# ESP12Block.net
KiCad netlist of a schematic drawn in EAGLE
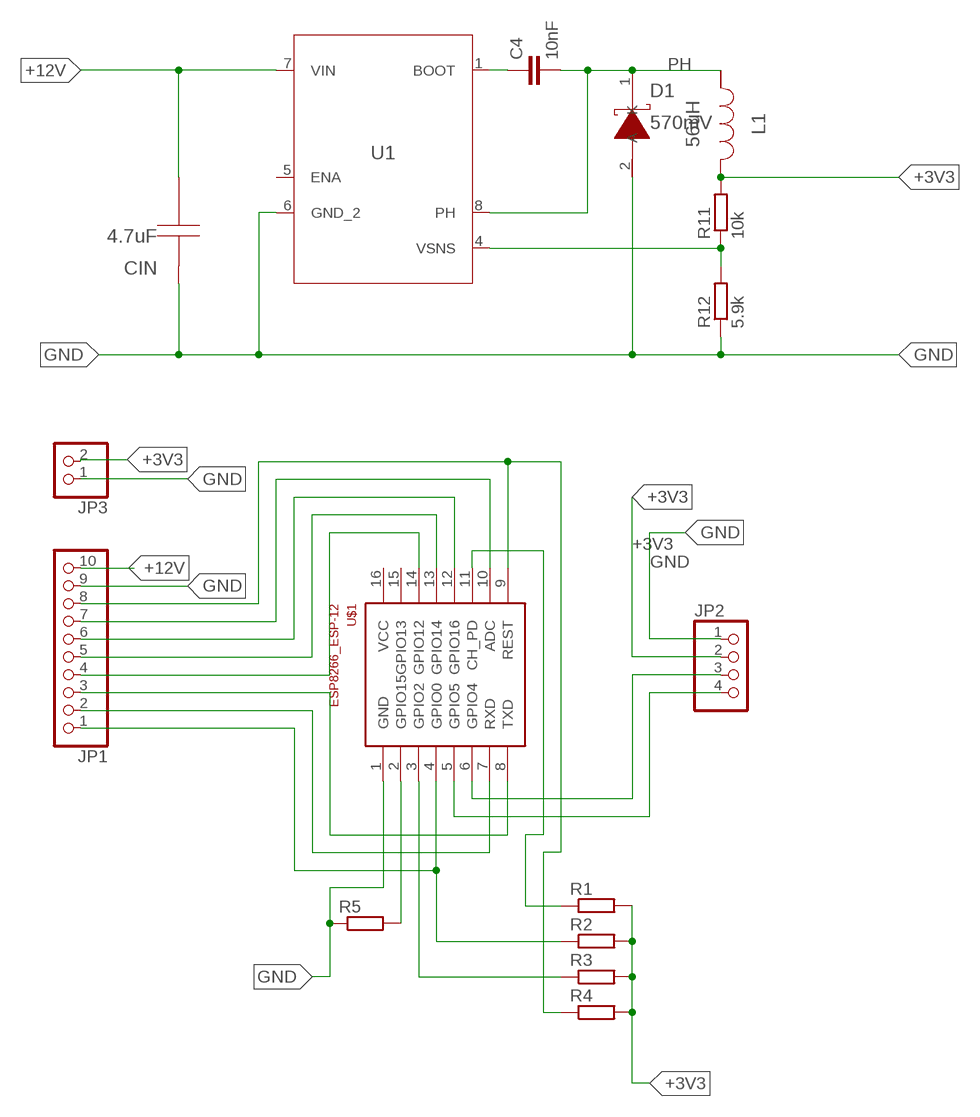
[diagram p0: schematic, sheet 1]

(export (version "E")
  (design (tool "Eeschema 10.0.6"))
  (components
    (comp (ref "C4")
      (value "10nF")
      (footprint "eagle-import:C0805")
      (libsource (lib "eagle-import") (part "C-EUC0805"))
    )
    (comp (ref "CIN")
      (value "4.7uF")
      (footprint "eagle-import:1206")
      (fields (field (name "MANUFACTURER_PART_NUMBER") "GRM31CR71H475KA12L"))
      (libsource (lib "eagle-import") (part "GRM31CR71H475KA12L"))
    )
    (comp (ref "D1")
      (value "570mV")
      (footprint "eagle-import:SOD-123F")
      (fields (field (name "MANUFACTURER_PART_NUMBER") "PMEG6010CEH115"))
      (libsource (lib "eagle-import") (part "PMEG6010CEH,115"))
    )
    (comp (ref "JP1")
      (value "PINHD-1X10_2.00")
      (footprint "eagle-import:1X10M")
      (libsource (lib "eagle-import") (part "PINHD-1X10_2.00"))
    )
    (comp (ref "JP2")
      (value "PINHD-1X4_2.54")
      (footprint "eagle-import:1X04")
      (libsource (lib "eagle-import") (part "PINHD-1X4_2.54"))
    )
    (comp (ref "JP3")
      (value "PINHD-1X2M")
      (footprint "eagle-import:1X02M")
      (libsource (lib "eagle-import") (part "PINHD-1X2M"))
    )
    (comp (ref "L1")
      (value "56uH")
      (footprint "eagle-import:IND_NPI75C")
      (fields (field (name "MANUFACTURER_PART_NUMBER") "NPI75C560KTRF"))
      (libsource (lib "eagle-import") (part "NPI75C560KTRF"))
    )
    (comp (ref "R1")
      (value "R-EU_M0805")
      (footprint "eagle-import:M0805")
      (libsource (lib "eagle-import") (part "R-EU_M0805"))
    )
    (comp (ref "R2")
      (value "R-EU_M0805")
      (footprint "eagle-import:M0805")
      (libsource (lib "eagle-import") (part "R-EU_M0805"))
    )
    (comp (ref "R3")
      (value "R-EU_M0805")
      (footprint "eagle-import:M0805")
      (libsource (lib "eagle-import") (part "R-EU_M0805"))
    )
    (comp (ref "R4")
      (value "R-EU_M0805")
      (footprint "eagle-import:M0805")
      (libsource (lib "eagle-import") (part "R-EU_M0805"))
    )
    (comp (ref "R5")
      (value "R-EU_M0805")
      (footprint "eagle-import:M0805")
      (libsource (lib "eagle-import") (part "R-EU_M0805"))
    )
    (comp (ref "R11")
      (value "10k")
      (footprint "eagle-import:R0805")
      (libsource (lib "eagle-import") (part "resistor_R-EU_R0805"))
    )
    (comp (ref "R12")
      (value "5.9k")
      (footprint "eagle-import:R0805")
      (libsource (lib "eagle-import") (part "resistor_R-EU_R0805"))
    )
    (comp (ref "U$1")
      (value "ESP8266_ESP-12")
      (footprint "eagle-import:ESP8266-ESP12")
      (libsource (lib "eagle-import") (part "ESP8266_ESP-12"))
    )
    (comp (ref "U1")
      (value "TPS5410DR")
      (footprint "eagle-import:M08A")
      (libsource (lib "eagle-import") (part "TPS5410DR"))
    )
  )
  (nets
    (net (code "1") (name "+3V3") (class "Default")
      (node (ref "JP2") (pin "2") (pinfunction "2_2") (pintype "passive"))
      (node (ref "JP3") (pin "2") (pinfunction "2_2") (pintype "passive"))
      (node (ref "L1") (pin "1") (pinfunction "1_1") (pintype "passive"))
      (node (ref "R1") (pin "2") (pinfunction "2_2") (pintype "passive"))
      (node (ref "R11") (pin "2") (pinfunction "2_2") (pintype "passive"))
      (node (ref "R2") (pin "2") (pinfunction "2_2") (pintype "passive"))
      (node (ref "R3") (pin "2") (pinfunction "2_2") (pintype "passive"))
      (node (ref "R4") (pin "2") (pinfunction "2_2") (pintype "passive"))
    )
    (net (code "2") (name "+12V") (class "Default")
      (node (ref "CIN") (pin "2") (pinfunction "2_2") (pintype "passive"))
      (node (ref "JP1") (pin "10") (pinfunction "10_10") (pintype "passive"))
      (node (ref "U1") (pin "7") (pinfunction "VIN_7") (pintype "passive"))
    )
    (net (code "3") (name "/PH") (class "Default")
      (node (ref "C4") (pin "2") (pinfunction "2_2") (pintype "passive"))
      (node (ref "D1") (pin "1") (pinfunction "K_1") (pintype "passive"))
      (node (ref "L1") (pin "2") (pinfunction "2_2") (pintype "passive"))
      (node (ref "U1") (pin "8") (pinfunction "PH_8") (pintype "passive"))
    )
    (net (code "4") (name "GND") (class "Default")
      (node (ref "CIN") (pin "1") (pinfunction "1_1") (pintype "passive"))
      (node (ref "D1") (pin "2") (pinfunction "A_2") (pintype "passive"))
      (node (ref "JP1") (pin "9") (pinfunction "9_9") (pintype "passive"))
      (node (ref "JP2") (pin "1") (pinfunction "1_1") (pintype "passive"))
      (node (ref "JP3") (pin "1") (pinfunction "1_1") (pintype "passive"))
      (node (ref "R12") (pin "1") (pinfunction "1_1") (pintype "passive"))
      (node (ref "R5") (pin "1") (pinfunction "1_1") (pintype "passive"))
      (node (ref "U$1") (pin "1") (pinfunction "GND_1") (pintype "bidirectional"))
      (node (ref "U1") (pin "6") (pinfunction "GND_2_6") (pintype "passive"))
    )
    (net (code "5") (name "Net-(U$1-ADC)") (class "Default")
      (node (ref "JP1") (pin "7") (pinfunction "7_7") (pintype "passive"))
      (node (ref "U$1") (pin "10") (pinfunction "ADC_10") (pintype "bidirectional"))
    )
    (net (code "6") (name "Net-(U$1-CH_PD)") (class "Default")
      (node (ref "R1") (pin "1") (pinfunction "1_1") (pintype "passive"))
      (node (ref "U$1") (pin "11") (pinfunction "CH_PD_11") (pintype "bidirectional"))
    )
    (net (code "7") (name "Net-(U$1-GPIO0)") (class "Default")
      (node (ref "JP1") (pin "1") (pinfunction "1_1") (pintype "passive"))
      (node (ref "R2") (pin "1") (pinfunction "1_1") (pintype "passive"))
      (node (ref "U$1") (pin "4") (pinfunction "GPIO0_4") (pintype "bidirectional"))
    )
    (net (code "8") (name "Net-(U$1-GPIO2)") (class "Default")
      (node (ref "R3") (pin "1") (pinfunction "1_1") (pintype "passive"))
      (node (ref "U$1") (pin "3") (pinfunction "GPIO2_3") (pintype "bidirectional"))
    )
    (net (code "9") (name "Net-(U$1-GPIO4)") (class "Default")
      (node (ref "JP2") (pin "3") (pinfunction "3_3") (pintype "passive"))
      (node (ref "U$1") (pin "6") (pinfunction "GPIO4_6") (pintype "bidirectional"))
    )
    (net (code "10") (name "Net-(U$1-GPIO5)") (class "Default")
      (node (ref "JP2") (pin "4") (pinfunction "4_4") (pintype "passive"))
      (node (ref "U$1") (pin "5") (pinfunction "GPIO5_5") (pintype "bidirectional"))
    )
    (net (code "11") (name "Net-(U$1-GPIO12)") (class "Default")
      (node (ref "JP1") (pin "4") (pinfunction "4_4") (pintype "passive"))
      (node (ref "U$1") (pin "14") (pinfunction "GPIO12_14") (pintype "bidirectional"))
    )
    (net (code "12") (name "Net-(U$1-GPIO14)") (class "Default")
      (node (ref "JP1") (pin "5") (pinfunction "5_5") (pintype "passive"))
      (node (ref "U$1") (pin "13") (pinfunction "GPIO14_13") (pintype "bidirectional"))
    )
    (net (code "13") (name "Net-(U$1-GPIO15)") (class "Default")
      (node (ref "R5") (pin "2") (pinfunction "2_2") (pintype "passive"))
      (node (ref "U$1") (pin "2") (pinfunction "GPIO15_2") (pintype "bidirectional"))
    )
    (net (code "14") (name "Net-(U$1-GPIO16)") (class "Default")
      (node (ref "JP1") (pin "6") (pinfunction "6_6") (pintype "passive"))
      (node (ref "U$1") (pin "12") (pinfunction "GPIO16_12") (pintype "bidirectional"))
    )
    (net (code "15") (name "Net-(U$1-REST)") (class "Default")
      (node (ref "JP1") (pin "8") (pinfunction "8_8") (pintype "passive"))
      (node (ref "R4") (pin "1") (pinfunction "1_1") (pintype "passive"))
      (node (ref "U$1") (pin "9") (pinfunction "REST_9") (pintype "bidirectional"))
    )
    (net (code "16") (name "Net-(U$1-RXD)") (class "Default")
      (node (ref "JP1") (pin "2") (pinfunction "2_2") (pintype "passive"))
      (node (ref "U$1") (pin "7") (pinfunction "RXD_7") (pintype "bidirectional"))
    )
    (net (code "17") (name "Net-(U$1-TXD)") (class "Default")
      (node (ref "JP1") (pin "3") (pinfunction "3_3") (pintype "passive"))
      (node (ref "U$1") (pin "8") (pinfunction "TXD_8") (pintype "bidirectional"))
    )
    (net (code "18") (name "Net-(U1-BOOT)") (class "Default")
      (node (ref "C4") (pin "1") (pinfunction "1_1") (pintype "passive"))
      (node (ref "U1") (pin "1") (pinfunction "BOOT_1") (pintype "passive"))
    )
    (net (code "19") (name "Net-(U1-VSNS)") (class "Default")
      (node (ref "R11") (pin "1") (pinfunction "1_1") (pintype "passive"))
      (node (ref "R12") (pin "2") (pinfunction "2_2") (pintype "passive"))
      (node (ref "U1") (pin "4") (pinfunction "VSNS_4") (pintype "passive"))
    )
    (net (code "20") (name "unconnected-(U$1-GPIO13-Pad15)") (class "Default")
      (node (ref "U$1") (pin "15") (pinfunction "GPIO13_15") (pintype "bidirectional"))
    )
    (net (code "21") (name "unconnected-(U$1-VCC-Pad16)") (class "Default")
      (node (ref "U$1") (pin "16") (pinfunction "VCC_16") (pintype "bidirectional"))
    )
    (net (code "22") (name "unconnected-(U1-ENA-Pad5)") (class "Default")
      (node (ref "U1") (pin "5") (pinfunction "ENA_5") (pintype "passive"))
    )
  )
)
